# ServoDriver.net
KiCad netlist of a schematic drawn in EasyEDA Pro
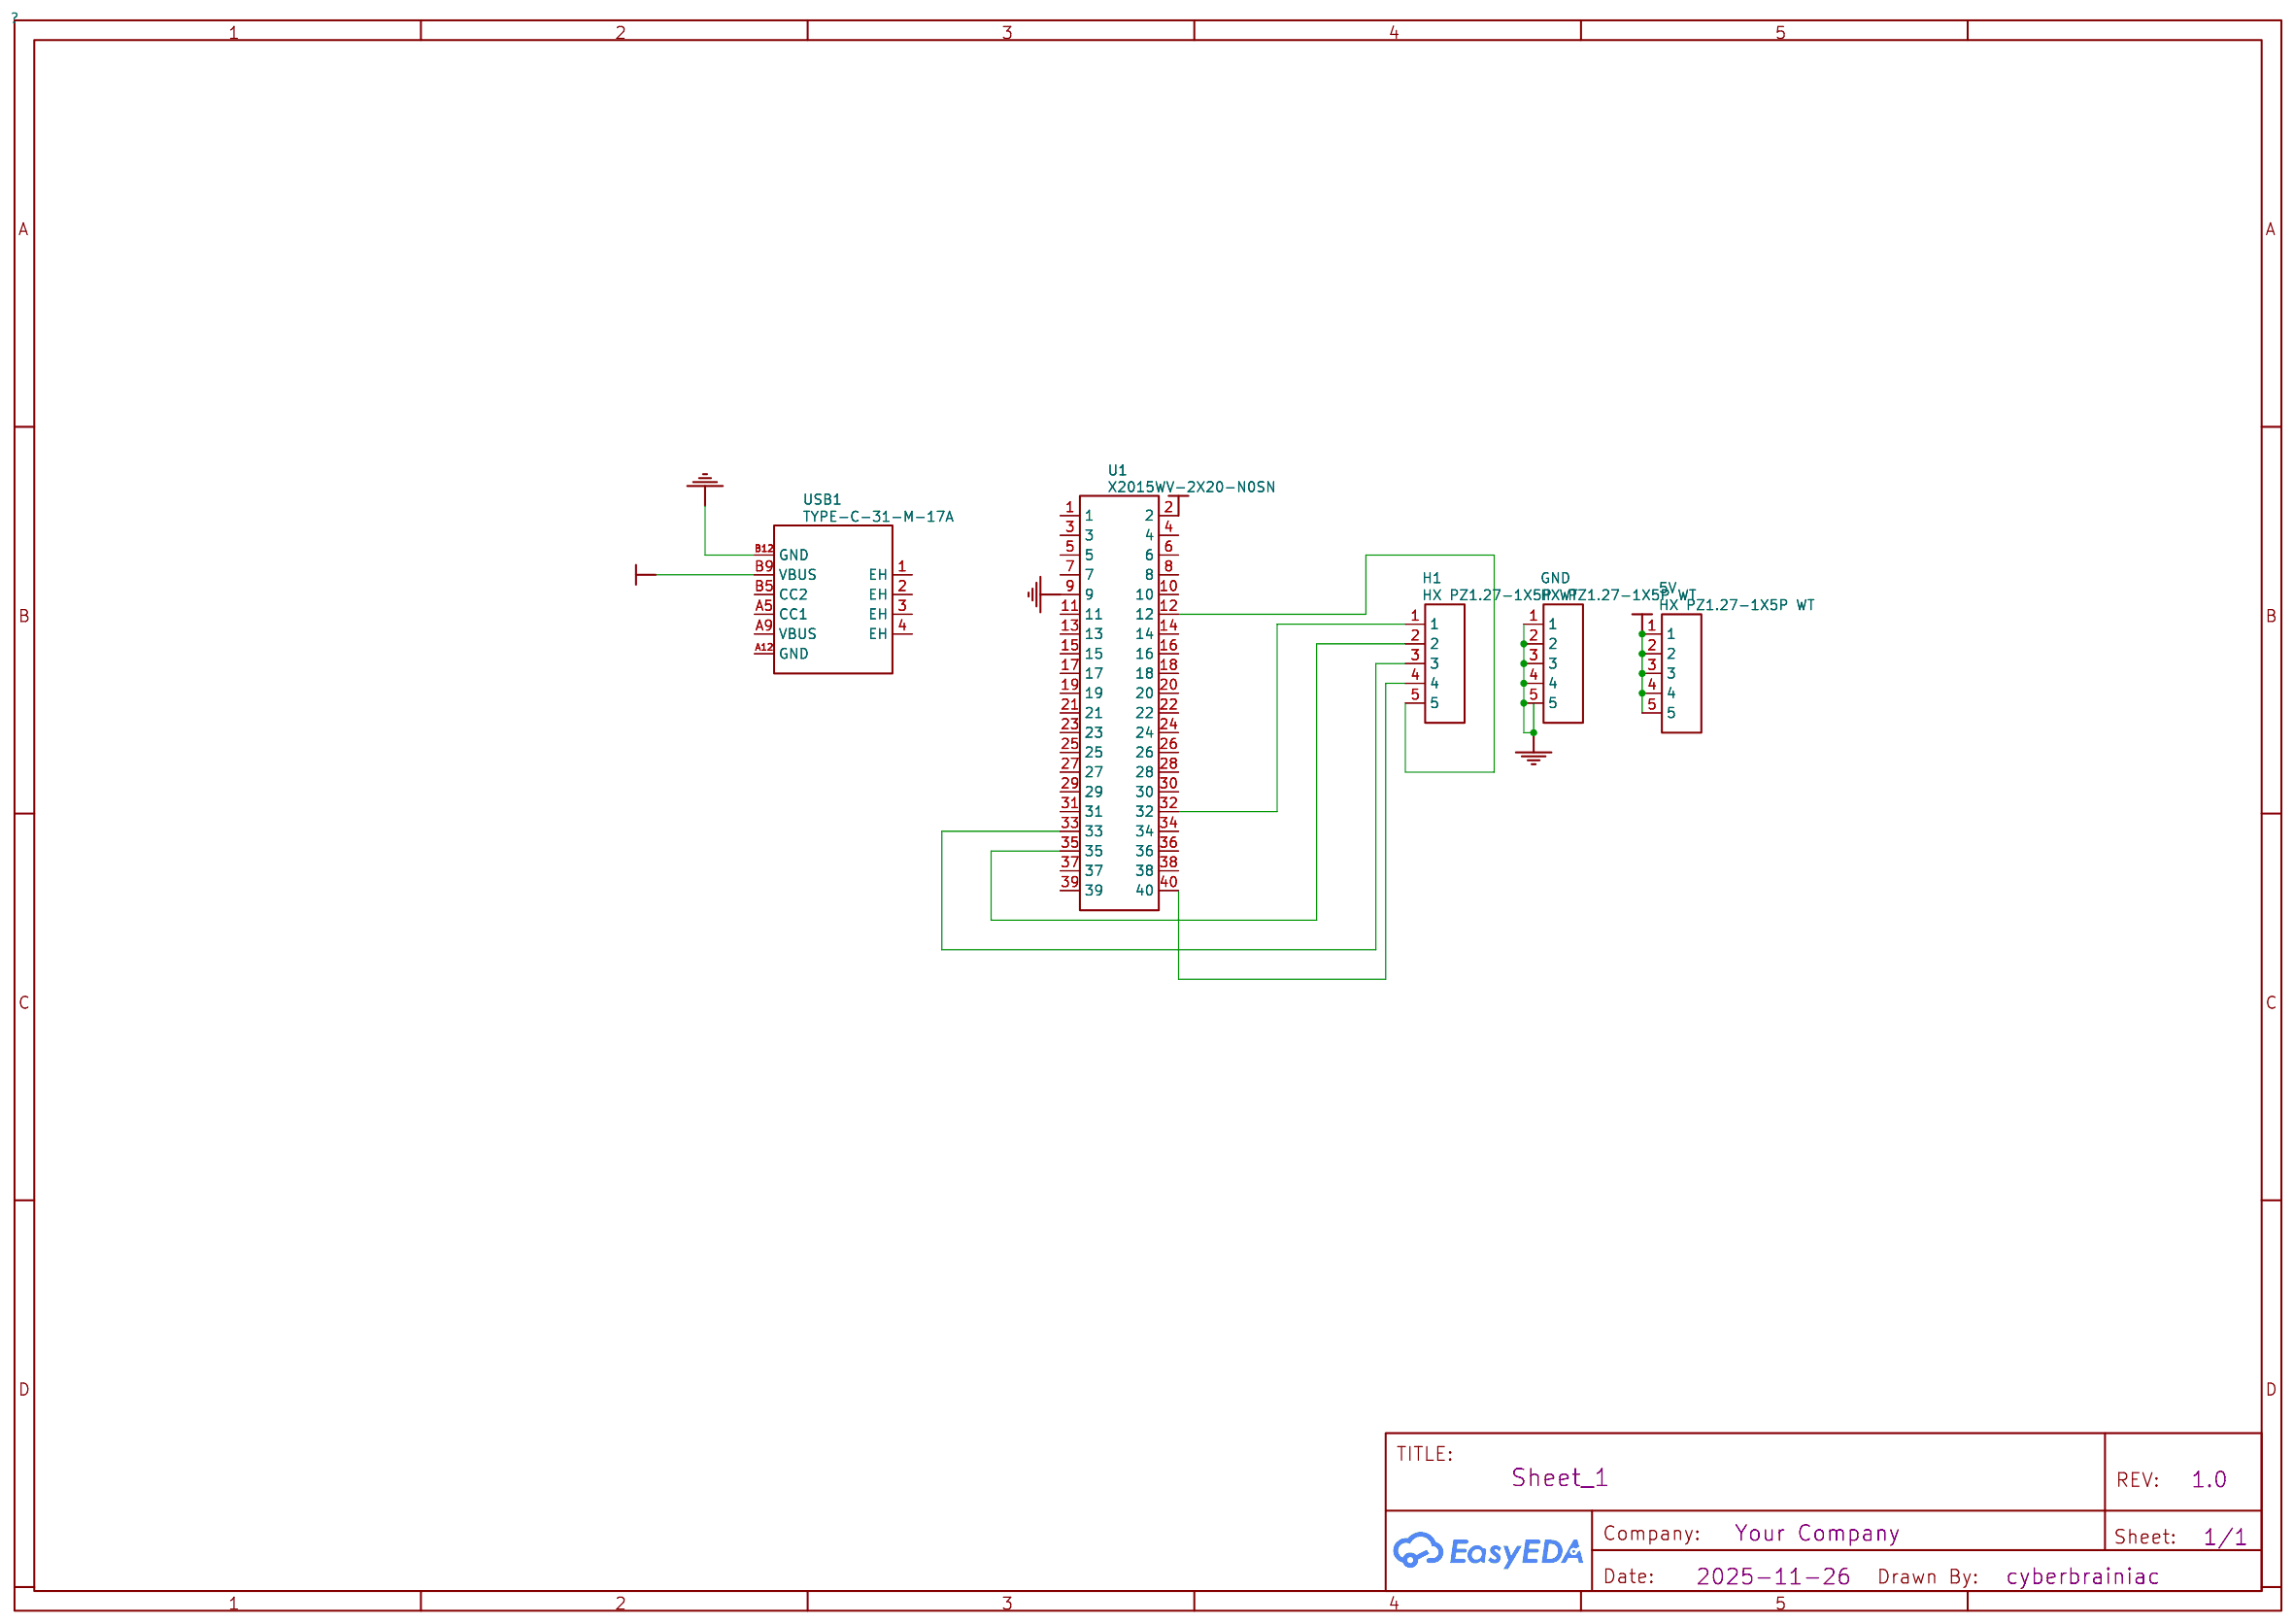
[diagram p0: schematic sheet]

(export (version "E")
  (design (tool "Eeschema 10.0.6"))
  (components
    (comp (ref "5V")
      (value "HX PZ1.27-1X5P WT")
      (footprint "easyedapro:HDR-SMD_5P-P1.27-HX-PZ1.27-1X5P-WT")
      (fields
        (field (name "Manufacturer Part") "HX PZ1.27-1x5P WT")
        (field (name "Manufacturer") "hanxia(韩下)")
        (field (name "Contributor") "lcsc")
      )
      (libsource (lib "easyedapro") (part "HX PZ1.27-1X5P WT"))
    )
    (comp (ref "GND")
      (value "HX PZ1.27-1X5P WT")
      (footprint "easyedapro:HDR-SMD_5P-P1.27-HX-PZ1.27-1X5P-WT")
      (fields
        (field (name "Manufacturer Part") "HX PZ1.27-1x5P WT")
        (field (name "Manufacturer") "hanxia(韩下)")
        (field (name "Contributor") "lcsc")
      )
      (libsource (lib "easyedapro") (part "HX PZ1.27-1X5P WT"))
    )
    (comp (ref "H1")
      (value "HX PZ1.27-1X5P WT")
      (footprint "easyedapro:HDR-SMD_5P-P1.27-HX-PZ1.27-1X5P-WT")
      (fields
        (field (name "Manufacturer Part") "HX PZ1.27-1x5P WT")
        (field (name "Manufacturer") "hanxia(韩下)")
        (field (name "Contributor") "lcsc")
      )
      (libsource (lib "easyedapro") (part "HX PZ1.27-1X5P WT"))
    )
    (comp (ref "U1")
      (value "X2015WV-2X20-N0SN")
      (footprint "easyedapro:CONN-TH_X2015WV-2X20-N0SN")
      (fields
        (field (name "Manufacturer Part") "X2015WV-2x20-46SN")
        (field (name "Manufacturer") "XKB Connection(中国星坤)")
        (field (name "Contributor") "LCSC")
      )
      (libsource (lib "easyedapro") (part "X2015WV-2X20-N0SN"))
    )
    (comp (ref "USB1")
      (value "TYPE-C-31-M-17A")
      (footprint "easyedapro:TYPE-C-SMD_TYPE-C-31-M-17A")
      (fields (field (name "Manufacturer") "韩国韩荣") (field (name "Contributor") "lcsc"))
      (libsource (lib "easyedapro") (part "TYPE-C-31-M-17A"))
    )
  )
  (nets
    (net (code "1") (name "+5V") (class "Default")
      (node (ref "5V") (pin "1") (pinfunction "1_1") (pintype "unspecified"))
      (node (ref "5V") (pin "2") (pinfunction "2_2") (pintype "unspecified"))
      (node (ref "5V") (pin "3") (pinfunction "3_3") (pintype "unspecified"))
      (node (ref "5V") (pin "4") (pinfunction "4_4") (pintype "unspecified"))
      (node (ref "5V") (pin "5") (pinfunction "5_5") (pintype "unspecified"))
      (node (ref "U1") (pin "2") (pinfunction "2_2") (pintype "unspecified"))
      (node (ref "USB1") (pin "B9") (pinfunction "VBUS_B9") (pintype "unspecified"))
    )
    (net (code "2") (name "GND") (class "Default")
      (node (ref "GND") (pin "1") (pinfunction "1_1") (pintype "unspecified"))
      (node (ref "GND") (pin "2") (pinfunction "2_2") (pintype "unspecified"))
      (node (ref "GND") (pin "3") (pinfunction "3_3") (pintype "unspecified"))
      (node (ref "GND") (pin "4") (pinfunction "4_4") (pintype "unspecified"))
      (node (ref "GND") (pin "5") (pinfunction "5_5") (pintype "unspecified"))
      (node (ref "U1") (pin "9") (pinfunction "9_9") (pintype "unspecified"))
      (node (ref "USB1") (pin "B12") (pinfunction "GND_B12") (pintype "unspecified"))
    )
    (net (code "3") (name "Net-(H1-Pad1)") (class "Default")
      (node (ref "H1") (pin "1") (pinfunction "1_1") (pintype "unspecified"))
      (node (ref "U1") (pin "32") (pinfunction "32_32") (pintype "unspecified"))
    )
    (net (code "4") (name "Net-(H1-Pad2)") (class "Default")
      (node (ref "H1") (pin "2") (pinfunction "2_2") (pintype "unspecified"))
      (node (ref "U1") (pin "35") (pinfunction "35_35") (pintype "unspecified"))
    )
    (net (code "5") (name "Net-(H1-Pad3)") (class "Default")
      (node (ref "H1") (pin "3") (pinfunction "3_3") (pintype "unspecified"))
      (node (ref "U1") (pin "33") (pinfunction "33_33") (pintype "unspecified"))
    )
    (net (code "6") (name "Net-(H1-Pad4)") (class "Default")
      (node (ref "H1") (pin "4") (pinfunction "4_4") (pintype "unspecified"))
      (node (ref "U1") (pin "40") (pinfunction "40_40") (pintype "unspecified"))
    )
    (net (code "7") (name "Net-(H1-Pad5)") (class "Default")
      (node (ref "H1") (pin "5") (pinfunction "5_5") (pintype "unspecified"))
      (node (ref "U1") (pin "12") (pinfunction "12_12") (pintype "unspecified"))
    )
    (net (code "8") (name "unconnected-(U1-Pad1)") (class "Default")
      (node (ref "U1") (pin "1") (pinfunction "1_1") (pintype "unspecified"))
    )
    (net (code "9") (name "unconnected-(U1-Pad3)") (class "Default")
      (node (ref "U1") (pin "3") (pinfunction "3_3") (pintype "unspecified"))
    )
    (net (code "10") (name "unconnected-(U1-Pad4)") (class "Default")
      (node (ref "U1") (pin "4") (pinfunction "4_4") (pintype "unspecified"))
    )
    (net (code "11") (name "unconnected-(U1-Pad5)") (class "Default")
      (node (ref "U1") (pin "5") (pinfunction "5_5") (pintype "unspecified"))
    )
    (net (code "12") (name "unconnected-(U1-Pad6)") (class "Default")
      (node (ref "U1") (pin "6") (pinfunction "6_6") (pintype "unspecified"))
    )
    (net (code "13") (name "unconnected-(U1-Pad7)") (class "Default")
      (node (ref "U1") (pin "7") (pinfunction "7_7") (pintype "unspecified"))
    )
    (net (code "14") (name "unconnected-(U1-Pad8)") (class "Default")
      (node (ref "U1") (pin "8") (pinfunction "8_8") (pintype "unspecified"))
    )
    (net (code "15") (name "unconnected-(U1-Pad10)") (class "Default")
      (node (ref "U1") (pin "10") (pinfunction "10_10") (pintype "unspecified"))
    )
    (net (code "16") (name "unconnected-(U1-Pad11)") (class "Default")
      (node (ref "U1") (pin "11") (pinfunction "11_11") (pintype "unspecified"))
    )
    (net (code "17") (name "unconnected-(U1-Pad13)") (class "Default")
      (node (ref "U1") (pin "13") (pinfunction "13_13") (pintype "unspecified"))
    )
    (net (code "18") (name "unconnected-(U1-Pad14)") (class "Default")
      (node (ref "U1") (pin "14") (pinfunction "14_14") (pintype "unspecified"))
    )
    (net (code "19") (name "unconnected-(U1-Pad15)") (class "Default")
      (node (ref "U1") (pin "15") (pinfunction "15_15") (pintype "unspecified"))
    )
    (net (code "20") (name "unconnected-(U1-Pad16)") (class "Default")
      (node (ref "U1") (pin "16") (pinfunction "16_16") (pintype "unspecified"))
    )
    (net (code "21") (name "unconnected-(U1-Pad17)") (class "Default")
      (node (ref "U1") (pin "17") (pinfunction "17_17") (pintype "unspecified"))
    )
    (net (code "22") (name "unconnected-(U1-Pad18)") (class "Default")
      (node (ref "U1") (pin "18") (pinfunction "18_18") (pintype "unspecified"))
    )
    (net (code "23") (name "unconnected-(U1-Pad19)") (class "Default")
      (node (ref "U1") (pin "19") (pinfunction "19_19") (pintype "unspecified"))
    )
    (net (code "24") (name "unconnected-(U1-Pad20)") (class "Default")
      (node (ref "U1") (pin "20") (pinfunction "20_20") (pintype "unspecified"))
    )
    (net (code "25") (name "unconnected-(U1-Pad21)") (class "Default")
      (node (ref "U1") (pin "21") (pinfunction "21_21") (pintype "unspecified"))
    )
    (net (code "26") (name "unconnected-(U1-Pad22)") (class "Default")
      (node (ref "U1") (pin "22") (pinfunction "22_22") (pintype "unspecified"))
    )
    (net (code "27") (name "unconnected-(U1-Pad23)") (class "Default")
      (node (ref "U1") (pin "23") (pinfunction "23_23") (pintype "unspecified"))
    )
    (net (code "28") (name "unconnected-(U1-Pad24)") (class "Default")
      (node (ref "U1") (pin "24") (pinfunction "24_24") (pintype "unspecified"))
    )
    (net (code "29") (name "unconnected-(U1-Pad25)") (class "Default")
      (node (ref "U1") (pin "25") (pinfunction "25_25") (pintype "unspecified"))
    )
    (net (code "30") (name "unconnected-(U1-Pad26)") (class "Default")
      (node (ref "U1") (pin "26") (pinfunction "26_26") (pintype "unspecified"))
    )
    (net (code "31") (name "unconnected-(U1-Pad27)") (class "Default")
      (node (ref "U1") (pin "27") (pinfunction "27_27") (pintype "unspecified"))
    )
    (net (code "32") (name "unconnected-(U1-Pad28)") (class "Default")
      (node (ref "U1") (pin "28") (pinfunction "28_28") (pintype "unspecified"))
    )
    (net (code "33") (name "unconnected-(U1-Pad29)") (class "Default")
      (node (ref "U1") (pin "29") (pinfunction "29_29") (pintype "unspecified"))
    )
    (net (code "34") (name "unconnected-(U1-Pad30)") (class "Default")
      (node (ref "U1") (pin "30") (pinfunction "30_30") (pintype "unspecified"))
    )
    (net (code "35") (name "unconnected-(U1-Pad31)") (class "Default")
      (node (ref "U1") (pin "31") (pinfunction "31_31") (pintype "unspecified"))
    )
    (net (code "36") (name "unconnected-(U1-Pad34)") (class "Default")
      (node (ref "U1") (pin "34") (pinfunction "34_34") (pintype "unspecified"))
    )
    (net (code "37") (name "unconnected-(U1-Pad36)") (class "Default")
      (node (ref "U1") (pin "36") (pinfunction "36_36") (pintype "unspecified"))
    )
    (net (code "38") (name "unconnected-(U1-Pad37)") (class "Default")
      (node (ref "U1") (pin "37") (pinfunction "37_37") (pintype "unspecified"))
    )
    (net (code "39") (name "unconnected-(U1-Pad38)") (class "Default")
      (node (ref "U1") (pin "38") (pinfunction "38_38") (pintype "unspecified"))
    )
    (net (code "40") (name "unconnected-(U1-Pad39)") (class "Default")
      (node (ref "U1") (pin "39") (pinfunction "39_39") (pintype "unspecified"))
    )
    (net (code "41") (name "unconnected-(USB1-CC1-PadA5)") (class "Default")
      (node (ref "USB1") (pin "A5") (pinfunction "CC1_A5") (pintype "unspecified"))
    )
    (net (code "42") (name "unconnected-(USB1-CC2-PadB5)") (class "Default")
      (node (ref "USB1") (pin "B5") (pinfunction "CC2_B5") (pintype "unspecified"))
    )
    (net (code "43") (name "unconnected-(USB1-EH-Pad1)") (class "Default")
      (node (ref "USB1") (pin "1") (pinfunction "EH_1") (pintype "unspecified"))
    )
    (net (code "44") (name "unconnected-(USB1-EH-Pad2)") (class "Default")
      (node (ref "USB1") (pin "2") (pinfunction "EH_2") (pintype "unspecified"))
    )
    (net (code "45") (name "unconnected-(USB1-EH-Pad3)") (class "Default")
      (node (ref "USB1") (pin "3") (pinfunction "EH_3") (pintype "unspecified"))
    )
    (net (code "46") (name "unconnected-(USB1-EH-Pad4)") (class "Default")
      (node (ref "USB1") (pin "4") (pinfunction "EH_4") (pintype "unspecified"))
    )
    (net (code "47") (name "unconnected-(USB1-GND-PadA12)") (class "Default")
      (node (ref "USB1") (pin "A12") (pinfunction "GND_A12") (pintype "unspecified"))
    )
    (net (code "48") (name "unconnected-(USB1-VBUS-PadA9)") (class "Default")
      (node (ref "USB1") (pin "A9") (pinfunction "VBUS_A9") (pintype "unspecified"))
    )
  )
)
